# CPU.net
KiCad netlist of a schematic drawn in Altium Designer
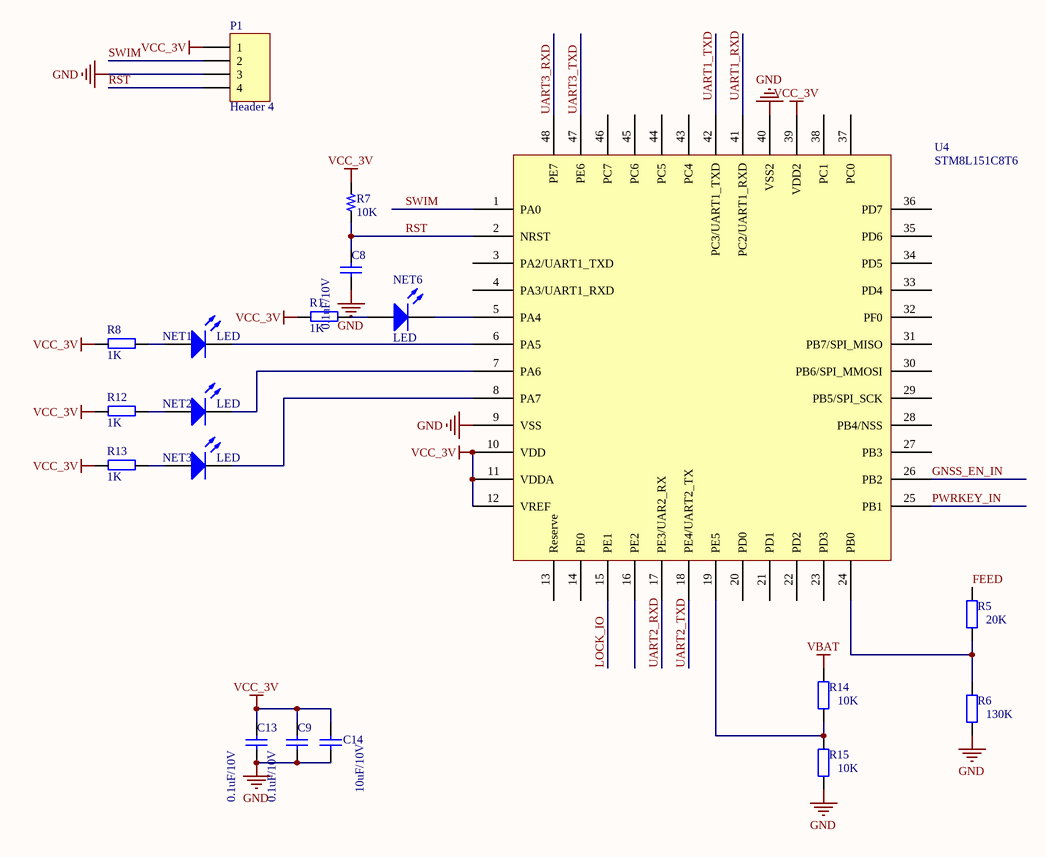
[diagram p0: CPU.SchDoc]

(export (version "E")
  (design (tool "Eeschema 10.0.6"))
  (components
    (comp (ref "C8")
      (value "0.1uF/10V")
      (footprint "0603C")
      (description "Capacitor")
      (fields (field (name "PUBLISHER") "Altium Limited"))
      (libsource (lib "Miscellaneous Devices") (part "Cap"))
    )
    (comp (ref "C9")
      (value "0.1uF/10V")
      (footprint "0603C")
      (description "Capacitor")
      (fields (field (name "PUBLISHER") "Altium Limited"))
      (libsource (lib "Miscellaneous Devices") (part "Cap"))
    )
    (comp (ref "C13")
      (value "0.1uF/10V")
      (footprint "0603C")
      (description "Capacitor")
      (fields (field (name "PUBLISHER") "Altium Limited"))
      (libsource (lib "Miscellaneous Devices") (part "Cap"))
    )
    (comp (ref "C14")
      (value "10uF/10V")
      (footprint "0603C")
      (description "Capacitor")
      (fields (field (name "PUBLISHER") "Altium Limited"))
      (libsource (lib "Miscellaneous Devices") (part "Cap"))
    )
    (comp (ref "NET1")
      (value "LED")
      (footprint "0603LED")
      (description "Typical RED, GREEN, YELLOW, AMBER GaAs LED")
      (fields (field (name "PUBLISHER") "Altium Limited"))
      (libsource (lib "SIM800C 原理图库") (part "LED2"))
    )
    (comp (ref "NET2")
      (value "LED")
      (footprint "0603LED")
      (description "Typical RED, GREEN, YELLOW, AMBER GaAs LED")
      (fields (field (name "PUBLISHER") "Altium Limited"))
      (libsource (lib "SIM800C 原理图库") (part "LED2"))
    )
    (comp (ref "NET3")
      (value "LED")
      (footprint "0603LED")
      (description "Typical RED, GREEN, YELLOW, AMBER GaAs LED")
      (fields (field (name "PUBLISHER") "Altium Limited"))
      (libsource (lib "SIM800C 原理图库") (part "LED2"))
    )
    (comp (ref "NET6")
      (value "LED")
      (footprint "0603LED")
      (description "Typical RED, GREEN, YELLOW, AMBER GaAs LED")
      (fields (field (name "PUBLISHER") "Altium Limited"))
      (libsource (lib "SIM800C 原理图库") (part "LED2"))
    )
    (comp (ref "P1")
      (value "Header 4")
      (footprint "HDR1X4")
      (description "Header, 4-Pin")
      (fields (field (name "PUBLISHER") "Altium Limited"))
      (libsource (lib "Miscellaneous Connectors") (part "Header 4"))
    )
    (comp (ref "R1") (value "1K") (footprint "0603r") (libsource (lib "SIM800C 原理图库") (part "R")))
    (comp (ref "R5")
      (value "20K")
      (footprint "0603R")
      (description "Resistor")
      (fields (field (name "PUBLISHER") "Altium Limited"))
      (libsource (lib "Miscellaneous Devices") (part "Res2"))
    )
    (comp (ref "R6")
      (value "130K")
      (footprint "0603R")
      (description "Resistor")
      (fields (field (name "PUBLISHER") "Altium Limited"))
      (libsource (lib "Miscellaneous Devices") (part "Res2"))
    )
    (comp (ref "R7") (value "10K") (footprint "0603R") (description "R") (libsource (lib "JRJ_1") (part "R")))
    (comp (ref "R8") (value "1K") (footprint "0603r") (libsource (lib "SIM800C 原理图库") (part "R")))
    (comp (ref "R12") (value "1K") (footprint "0603r") (libsource (lib "SIM800C 原理图库") (part "R")))
    (comp (ref "R13") (value "1K") (footprint "0603r") (libsource (lib "SIM800C 原理图库") (part "R")))
    (comp (ref "R14")
      (value "10K")
      (footprint "0603R")
      (description "Resistor")
      (fields (field (name "PUBLISHER") "Altium Limited"))
      (libsource (lib "Miscellaneous Devices") (part "Res2"))
    )
    (comp (ref "R15")
      (value "10K")
      (footprint "0603R")
      (description "Resistor")
      (fields (field (name "PUBLISHER") "Altium Limited"))
      (libsource (lib "Miscellaneous Devices") (part "Res2"))
    )
    (comp (ref "U4")
      (value "STM8L151C8T6")
      (footprint "TQFP-48")
      (libsource (lib "stm32") (part "STM8L151C8T6"))
    )
  )
  (nets
    (net (code "1") (name "/FEED") (class "Default")
      (node (ref "R5") (pin "1") (pinfunction "1_1") (pintype "passive"))
    )
    (net (code "2") (name "/GNSS_EN_IN") (class "Default")
      (node (ref "U4") (pin "26") (pinfunction "PB2_26") (pintype "passive"))
    )
    (net (code "3") (name "/LOCK_IO") (class "Default")
      (node (ref "U4") (pin "15") (pinfunction "PE1_15") (pintype "passive"))
    )
    (net (code "4") (name "/PWRKEY_IN") (class "Default")
      (node (ref "U4") (pin "25") (pinfunction "PB1_25") (pintype "passive"))
    )
    (net (code "5") (name "/RST") (class "Default")
      (node (ref "C8") (pin "1") (pinfunction "1_1") (pintype "passive"))
      (node (ref "P1") (pin "4") (pinfunction "4_4") (pintype "passive"))
      (node (ref "R7") (pin "1") (pintype "passive"))
      (node (ref "U4") (pin "2") (pinfunction "NRST_2") (pintype "passive"))
    )
    (net (code "6") (name "/SWIM") (class "Default")
      (node (ref "P1") (pin "2") (pinfunction "2_2") (pintype "passive"))
      (node (ref "U4") (pin "1") (pinfunction "PA0_1") (pintype "passive"))
    )
    (net (code "7") (name "/UART1_RXD") (class "Default")
      (node (ref "U4") (pin "41") (pinfunction "PC2/UART1_RXD_41") (pintype "passive"))
    )
    (net (code "8") (name "/UART1_TXD") (class "Default")
      (node (ref "U4") (pin "42") (pinfunction "PC3/UART1_TXD_42") (pintype "passive"))
    )
    (net (code "9") (name "/UART2_RXD") (class "Default")
      (node (ref "U4") (pin "17") (pinfunction "PE3/UAR2_RX_17") (pintype "passive"))
    )
    (net (code "10") (name "/UART2_TXD") (class "Default")
      (node (ref "U4") (pin "18") (pinfunction "PE4/UART2_TX_18") (pintype "passive"))
    )
    (net (code "11") (name "/UART3_RXD") (class "Default")
      (node (ref "U4") (pin "48") (pinfunction "PE7_48") (pintype "passive"))
    )
    (net (code "12") (name "/UART3_TXD") (class "Default")
      (node (ref "U4") (pin "47") (pinfunction "PE6_47") (pintype "passive"))
    )
    (net (code "13") (name "GND") (class "Default")
      (node (ref "C13") (pin "2") (pinfunction "2_2") (pintype "passive"))
      (node (ref "C14") (pin "1") (pinfunction "1_1") (pintype "passive"))
      (node (ref "C8") (pin "2") (pinfunction "2_2") (pintype "passive"))
      (node (ref "C9") (pin "2") (pinfunction "2_2") (pintype "passive"))
      (node (ref "P1") (pin "3") (pinfunction "3_3") (pintype "passive"))
      (node (ref "R15") (pin "2") (pinfunction "2_2") (pintype "passive"))
      (node (ref "R6") (pin "2") (pinfunction "2_2") (pintype "passive"))
      (node (ref "U4") (pin "40") (pinfunction "VSS2_40") (pintype "passive"))
      (node (ref "U4") (pin "9") (pinfunction "VSS_9") (pintype "passive"))
    )
    (net (code "14") (name "Net-(NET1-A)") (class "Default")
      (node (ref "NET1") (pin "1") (pinfunction "A_1") (pintype "passive"))
      (node (ref "R8") (pin "1") (pintype "passive"))
    )
    (net (code "15") (name "Net-(NET1-K)") (class "Default")
      (node (ref "NET1") (pin "2") (pinfunction "K_2") (pintype "passive"))
      (node (ref "U4") (pin "6") (pinfunction "PA5_6") (pintype "passive"))
    )
    (net (code "16") (name "Net-(NET2-A)") (class "Default")
      (node (ref "NET2") (pin "1") (pinfunction "A_1") (pintype "passive"))
      (node (ref "R12") (pin "1") (pintype "passive"))
    )
    (net (code "17") (name "Net-(NET2-K)") (class "Default")
      (node (ref "NET2") (pin "2") (pinfunction "K_2") (pintype "passive"))
      (node (ref "U4") (pin "7") (pinfunction "PA6_7") (pintype "passive"))
    )
    (net (code "18") (name "Net-(NET3-A)") (class "Default")
      (node (ref "NET3") (pin "1") (pinfunction "A_1") (pintype "passive"))
      (node (ref "R13") (pin "1") (pintype "passive"))
    )
    (net (code "19") (name "Net-(NET3-K)") (class "Default")
      (node (ref "NET3") (pin "2") (pinfunction "K_2") (pintype "passive"))
      (node (ref "U4") (pin "8") (pinfunction "PA7_8") (pintype "passive"))
    )
    (net (code "20") (name "Net-(NET6-A)") (class "Default")
      (node (ref "NET6") (pin "1") (pinfunction "A_1") (pintype "passive"))
      (node (ref "R1") (pin "1") (pintype "passive"))
    )
    (net (code "21") (name "Net-(NET6-K)") (class "Default")
      (node (ref "NET6") (pin "2") (pinfunction "K_2") (pintype "passive"))
      (node (ref "U4") (pin "5") (pinfunction "PA4_5") (pintype "passive"))
    )
    (net (code "22") (name "Net-(U4-PB0)") (class "Default")
      (node (ref "R5") (pin "2") (pinfunction "2_2") (pintype "passive"))
      (node (ref "R6") (pin "1") (pinfunction "1_1") (pintype "passive"))
      (node (ref "U4") (pin "24") (pinfunction "PB0_24") (pintype "passive"))
    )
    (net (code "23") (name "Net-(U4-PE5)") (class "Default")
      (node (ref "R14") (pin "2") (pinfunction "2_2") (pintype "passive"))
      (node (ref "R15") (pin "1") (pinfunction "1_1") (pintype "passive"))
      (node (ref "U4") (pin "19") (pinfunction "PE5_19") (pintype "passive"))
    )
    (net (code "24") (name "VBAT") (class "Default")
      (node (ref "R14") (pin "1") (pinfunction "1_1") (pintype "passive"))
    )
    (net (code "25") (name "VCC_3V") (class "Default")
      (node (ref "C13") (pin "1") (pinfunction "1_1") (pintype "passive"))
      (node (ref "C14") (pin "2") (pinfunction "2_2") (pintype "passive"))
      (node (ref "C9") (pin "1") (pinfunction "1_1") (pintype "passive"))
      (node (ref "P1") (pin "1") (pinfunction "1_1") (pintype "passive"))
      (node (ref "R1") (pin "2") (pintype "passive"))
      (node (ref "R12") (pin "2") (pintype "passive"))
      (node (ref "R13") (pin "2") (pintype "passive"))
      (node (ref "R7") (pin "2") (pintype "passive"))
      (node (ref "R8") (pin "2") (pintype "passive"))
      (node (ref "U4") (pin "10") (pinfunction "VDD_10") (pintype "passive"))
      (node (ref "U4") (pin "11") (pinfunction "VDDA_11") (pintype "passive"))
      (node (ref "U4") (pin "12") (pinfunction "VREF_12") (pintype "passive"))
      (node (ref "U4") (pin "39") (pinfunction "VDD2_39") (pintype "passive"))
    )
    (net (code "26") (name "unconnected-(U4-PA2{slash}UART1_TXD-Pad3)") (class "Default")
      (node (ref "U4") (pin "3") (pinfunction "PA2/UART1_TXD_3") (pintype "passive"))
    )
    (net (code "27") (name "unconnected-(U4-PA3{slash}UART1_RXD-Pad4)") (class "Default")
      (node (ref "U4") (pin "4") (pinfunction "PA3/UART1_RXD_4") (pintype "passive"))
    )
    (net (code "28") (name "unconnected-(U4-PB3-Pad27)") (class "Default")
      (node (ref "U4") (pin "27") (pinfunction "PB3_27") (pintype "passive"))
    )
    (net (code "29") (name "unconnected-(U4-PB4{slash}NSS-Pad28)") (class "Default")
      (node (ref "U4") (pin "28") (pinfunction "PB4/NSS_28") (pintype "passive"))
    )
    (net (code "30") (name "unconnected-(U4-PB5{slash}SPI_SCK-Pad29)") (class "Default")
      (node (ref "U4") (pin "29") (pinfunction "PB5/SPI_SCK_29") (pintype "passive"))
    )
    (net (code "31") (name "unconnected-(U4-PB6{slash}SPI_MMOSI-Pad30)") (class "Default")
      (node (ref "U4") (pin "30") (pinfunction "PB6/SPI_MMOSI_30") (pintype "passive"))
    )
    (net (code "32") (name "unconnected-(U4-PB7{slash}SPI_MISO-Pad31)") (class "Default")
      (node (ref "U4") (pin "31") (pinfunction "PB7/SPI_MISO_31") (pintype "passive"))
    )
    (net (code "33") (name "unconnected-(U4-PC0-Pad37)") (class "Default")
      (node (ref "U4") (pin "37") (pinfunction "PC0_37") (pintype "passive"))
    )
    (net (code "34") (name "unconnected-(U4-PC1-Pad38)") (class "Default")
      (node (ref "U4") (pin "38") (pinfunction "PC1_38") (pintype "passive"))
    )
    (net (code "35") (name "unconnected-(U4-PC4-Pad43)") (class "Default")
      (node (ref "U4") (pin "43") (pinfunction "PC4_43") (pintype "passive"))
    )
    (net (code "36") (name "unconnected-(U4-PC5-Pad44)") (class "Default")
      (node (ref "U4") (pin "44") (pinfunction "PC5_44") (pintype "passive"))
    )
    (net (code "37") (name "unconnected-(U4-PC6-Pad45)") (class "Default")
      (node (ref "U4") (pin "45") (pinfunction "PC6_45") (pintype "passive"))
    )
    (net (code "38") (name "unconnected-(U4-PC7-Pad46)") (class "Default")
      (node (ref "U4") (pin "46") (pinfunction "PC7_46") (pintype "passive"))
    )
    (net (code "39") (name "unconnected-(U4-PD0-Pad20)") (class "Default")
      (node (ref "U4") (pin "20") (pinfunction "PD0_20") (pintype "passive"))
    )
    (net (code "40") (name "unconnected-(U4-PD1-Pad21)") (class "Default")
      (node (ref "U4") (pin "21") (pinfunction "PD1_21") (pintype "passive"))
    )
    (net (code "41") (name "unconnected-(U4-PD2-Pad22)") (class "Default")
      (node (ref "U4") (pin "22") (pinfunction "PD2_22") (pintype "passive"))
    )
    (net (code "42") (name "unconnected-(U4-PD3-Pad23)") (class "Default")
      (node (ref "U4") (pin "23") (pinfunction "PD3_23") (pintype "passive"))
    )
    (net (code "43") (name "unconnected-(U4-PD4-Pad33)") (class "Default")
      (node (ref "U4") (pin "33") (pinfunction "PD4_33") (pintype "passive"))
    )
    (net (code "44") (name "unconnected-(U4-PD5-Pad34)") (class "Default")
      (node (ref "U4") (pin "34") (pinfunction "PD5_34") (pintype "passive"))
    )
    (net (code "45") (name "unconnected-(U4-PD6-Pad35)") (class "Default")
      (node (ref "U4") (pin "35") (pinfunction "PD6_35") (pintype "passive"))
    )
    (net (code "46") (name "unconnected-(U4-PD7-Pad36)") (class "Default")
      (node (ref "U4") (pin "36") (pinfunction "PD7_36") (pintype "passive"))
    )
    (net (code "47") (name "unconnected-(U4-PE0-Pad14)") (class "Default")
      (node (ref "U4") (pin "14") (pinfunction "PE0_14") (pintype "passive"))
    )
    (net (code "48") (name "unconnected-(U4-PE2-Pad16)") (class "Default")
      (node (ref "U4") (pin "16") (pinfunction "PE2_16") (pintype "passive"))
    )
    (net (code "49") (name "unconnected-(U4-PF0-Pad32)") (class "Default")
      (node (ref "U4") (pin "32") (pinfunction "PF0_32") (pintype "passive"))
    )
    (net (code "50") (name "unconnected-(U4-Reserve-Pad13)") (class "Default")
      (node (ref "U4") (pin "13") (pinfunction "Reserve_13") (pintype "passive"))
    )
  )
)
